# gige_phy.net
KiCad netlist of a schematic drawn in Altium Designer
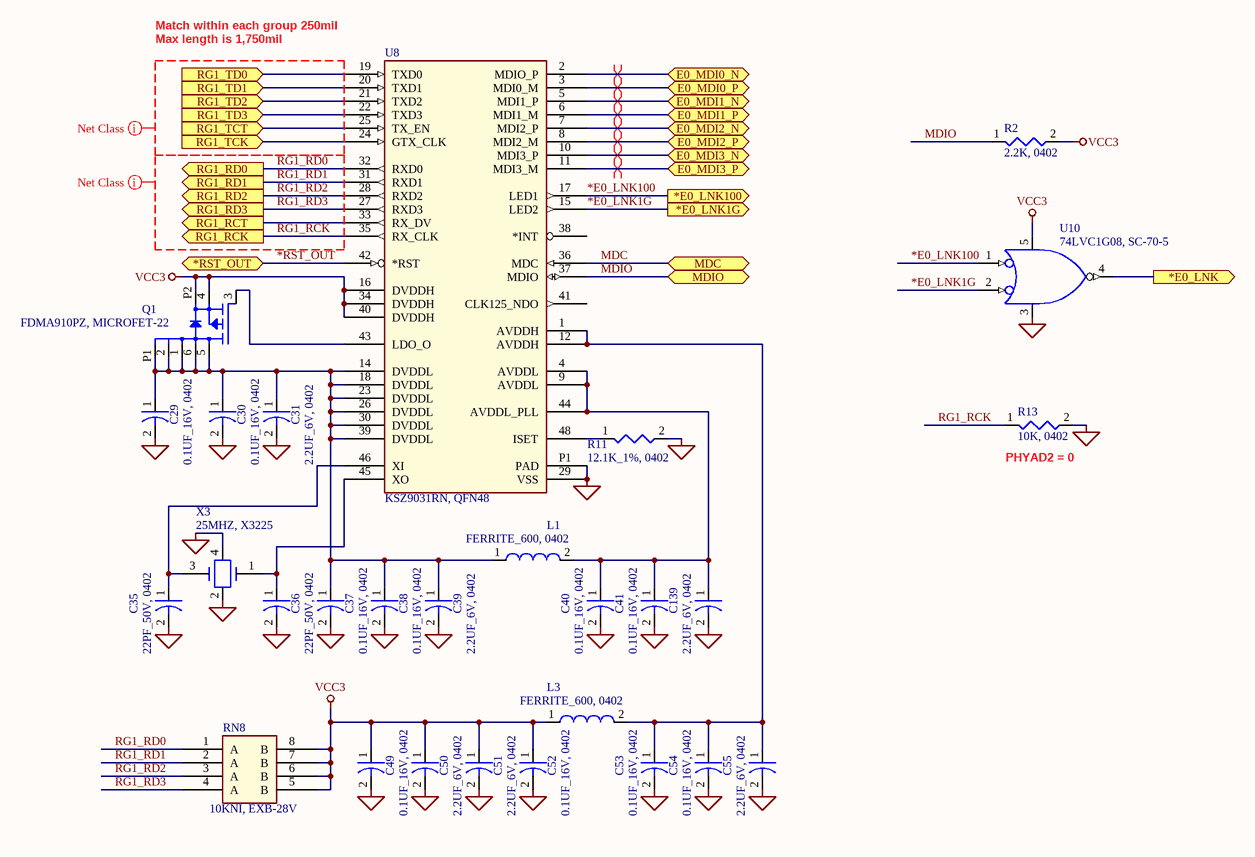
[diagram p0: gige_phy.SchDoc]

(export (version "E")
  (design (tool "Eeschema 10.0.6"))
  (components
    (comp (ref "C29")
      (value "0.1UF_16V, 0402")
      (footprint "0402C")
      (description "CAP - 0402 PKG")
      (libsource (lib "COGENT_Library") (part "0.1UF_16V, 0402"))
    )
    (comp (ref "C30")
      (value "0.1UF_16V, 0402")
      (footprint "0402C")
      (description "CAP - 0402 PKG")
      (libsource (lib "COGENT_Library") (part "0.1UF_16V, 0402"))
    )
    (comp (ref "C31")
      (value "2.2UF_6V, 0402")
      (footprint "0402C")
      (description "CAP - 0402 PKG")
      (libsource (lib "COGENT_Library") (part "2.2UF_6V, 0402"))
    )
    (comp (ref "C35")
      (value "22PF_50V, 0402")
      (footprint "0402C")
      (description "CAP - 0402 PKG")
      (libsource (lib "COGENT_Library") (part "22PF_50V, 0402"))
    )
    (comp (ref "C36")
      (value "22PF_50V, 0402")
      (footprint "0402C")
      (description "CAP - 0402 PKG")
      (libsource (lib "COGENT_Library") (part "22PF_50V, 0402"))
    )
    (comp (ref "C37")
      (value "0.1UF_16V, 0402")
      (footprint "0402C")
      (description "CAP - 0402 PKG")
      (libsource (lib "COGENT_Library") (part "0.1UF_16V, 0402"))
    )
    (comp (ref "C38")
      (value "0.1UF_16V, 0402")
      (footprint "0402C")
      (description "CAP - 0402 PKG")
      (libsource (lib "COGENT_Library") (part "0.1UF_16V, 0402"))
    )
    (comp (ref "C39")
      (value "2.2UF_6V, 0402")
      (footprint "0402C")
      (description "CAP - 0402 PKG")
      (libsource (lib "COGENT_Library") (part "2.2UF_6V, 0402"))
    )
    (comp (ref "C40")
      (value "0.1UF_16V, 0402")
      (footprint "0402C")
      (description "CAP - 0402 PKG")
      (libsource (lib "COGENT_Library") (part "0.1UF_16V, 0402"))
    )
    (comp (ref "C41")
      (value "0.1UF_16V, 0402")
      (footprint "0402C")
      (description "CAP - 0402 PKG")
      (libsource (lib "COGENT_Library") (part "0.1UF_16V, 0402"))
    )
    (comp (ref "C49")
      (value "0.1UF_16V, 0402")
      (footprint "0402C")
      (description "CAP - 0402 PKG")
      (libsource (lib "COGENT_Library") (part "0.1UF_16V, 0402"))
    )
    (comp (ref "C50")
      (value "2.2UF_6V, 0402")
      (footprint "0402C")
      (description "CAP - 0402 PKG")
      (libsource (lib "COGENT_Library") (part "2.2UF_6V, 0402"))
    )
    (comp (ref "C51")
      (value "2.2UF_6V, 0402")
      (footprint "0402C")
      (description "CAP - 0402 PKG")
      (libsource (lib "COGENT_Library") (part "2.2UF_6V, 0402"))
    )
    (comp (ref "C52")
      (value "0.1UF_16V, 0402")
      (footprint "0402C")
      (description "CAP - 0402 PKG")
      (libsource (lib "COGENT_Library") (part "0.1UF_16V, 0402"))
    )
    (comp (ref "C53")
      (value "0.1UF_16V, 0402")
      (footprint "0402C")
      (description "CAP - 0402 PKG")
      (libsource (lib "COGENT_Library") (part "0.1UF_16V, 0402"))
    )
    (comp (ref "C54")
      (value "0.1UF_16V, 0402")
      (footprint "0402C")
      (description "CAP - 0402 PKG")
      (libsource (lib "COGENT_Library") (part "0.1UF_16V, 0402"))
    )
    (comp (ref "C55")
      (value "2.2UF_6V, 0402")
      (footprint "0402C")
      (description "CAP - 0402 PKG")
      (libsource (lib "COGENT_Library") (part "2.2UF_6V, 0402"))
    )
    (comp (ref "C139")
      (value "2.2UF_6V, 0402")
      (footprint "0402C")
      (description "CAP - 0402 PKG")
      (libsource (lib "COGENT_Library") (part "2.2UF_6V, 0402"))
    )
    (comp (ref "L1")
      (value "FERRITE_600, 0402")
      (footprint "0402L")
      (description "FERRITE BEAD - 600 OHM, 300MA, 0402 PKG")
      (libsource (lib "COGENT_Library") (part "FERRITE_600, 0402"))
    )
    (comp (ref "L3")
      (value "FERRITE_600, 0402")
      (footprint "0402L")
      (description "FERRITE BEAD - 600 OHM, 300MA, 0402 PKG")
      (libsource (lib "COGENT_Library") (part "FERRITE_600, 0402"))
    )
    (comp (ref "Q1")
      (value "FDMA910PZ, MICROFET-22")
      (footprint "MICROFET-22")
      (description "P-FET - 20V, 7.2A @ 1.8Vgs, 34mohm")
      (libsource (lib "COGENT_Library") (part "FDMA910PZ, MICROFET-22"))
    )
    (comp (ref "R2")
      (value "2.2K, 0402")
      (footprint "0402R")
      (description "RES - 0402 PKG")
      (libsource (lib "COGENT_Library") (part "2.2K, 0402"))
    )
    (comp (ref "R11")
      (value "12.1K_1%, 0402")
      (footprint "0402R")
      (description "RES - 0402 PKG")
      (libsource (lib "COGENT_Library") (part "12.1K_1%, 0402"))
    )
    (comp (ref "R13")
      (value "10K, 0402")
      (footprint "0402R")
      (description "RES - 0402 PKG")
      (libsource (lib "COGENT_Library") (part "10K, 0402"))
    )
    (comp (ref "RN8")
      (value "10KNI, EXB-28V")
      (footprint "EXB-28V")
      (description "RES NET, 4 INDIVIDUAL, EXB-28V")
      (libsource (lib "COGENT_Library") (part "10KNI, EXB-28V"))
    )
    (comp (ref "U8")
      (value "KSZ9031RN, QFN48")
      (footprint "QFN48")
      (description "PHY - RGMII TO COPPER, 1.8V/3.3V I/O")
      (libsource (lib "COGENT_Library") (part "KSZ9031RN, QFN48"))
    )
    (comp (ref "U10")
      (value "74LVC1G08, SC-70-5")
      (footprint "SOT-353/SC-70-5")
      (description "GATE - 2-INPUT AND")
      (libsource (lib "COGENT_Library") (part "74LVC1G08, SC-70-5"))
    )
    (comp (ref "X3")
      (value "25MHZ, X3225")
      (footprint "X3225")
      (description "CRYSTAL - SMT, 3.2MM x 2.5MM, ABM8 PKG")
      (libsource (lib "COGENT_Library") (part "25MHZ, X3225"))
    )
  )
  (nets
    (net (code "1") (name "/*E0_LNK") (class "Default")
      (node (ref "U10") (pin "4") (pinfunction "Y_4") (pintype "output"))
    )
    (net (code "2") (name "/*E0_LNK1G") (class "Default")
      (node (ref "U10") (pin "2") (pinfunction "B_2") (pintype "input"))
      (node (ref "U8") (pin "15") (pinfunction "LED2_15") (pintype "output"))
    )
    (net (code "3") (name "/*E0_LNK100") (class "Default")
      (node (ref "U10") (pin "1") (pinfunction "A_1") (pintype "input"))
      (node (ref "U8") (pin "17") (pinfunction "LED1_17") (pintype "output"))
    )
    (net (code "4") (name "/*RST_OUT") (class "Default")
      (node (ref "U8") (pin "42") (pinfunction "*RST_42") (pintype "input"))
    )
    (net (code "5") (name "/E0_MDI0_N") (class "Default")
      (node (ref "U8") (pin "2") (pinfunction "MDIO_P_2") (pintype "passive"))
    )
    (net (code "6") (name "/E0_MDI0_P") (class "Default")
      (node (ref "U8") (pin "3") (pinfunction "MDI0_M_3") (pintype "passive"))
    )
    (net (code "7") (name "/E0_MDI1_N") (class "Default")
      (node (ref "U8") (pin "5") (pinfunction "MDI1_P_5") (pintype "passive"))
    )
    (net (code "8") (name "/E0_MDI1_P") (class "Default")
      (node (ref "U8") (pin "6") (pinfunction "MDI1_M_6") (pintype "passive"))
    )
    (net (code "9") (name "/E0_MDI2_N") (class "Default")
      (node (ref "U8") (pin "7") (pinfunction "MDI2_P_7") (pintype "passive"))
    )
    (net (code "10") (name "/E0_MDI2_P") (class "Default")
      (node (ref "U8") (pin "8") (pinfunction "MDI2_M_8") (pintype "passive"))
    )
    (net (code "11") (name "/E0_MDI3_N") (class "Default")
      (node (ref "U8") (pin "10") (pinfunction "MDI3_P_10") (pintype "passive"))
    )
    (net (code "12") (name "/E0_MDI3_P") (class "Default")
      (node (ref "U8") (pin "11") (pinfunction "MDI3_M_11") (pintype "passive"))
    )
    (net (code "13") (name "/MDC") (class "Default")
      (node (ref "U8") (pin "36") (pinfunction "MDC_36") (pintype "input"))
    )
    (net (code "14") (name "/MDIO") (class "Default")
      (node (ref "R2") (pin "1") (pinfunction "1_1") (pintype "passive"))
      (node (ref "U8") (pin "37") (pinfunction "MDIO_37") (pintype "bidirectional"))
    )
    (net (code "15") (name "/RG1_RCK") (class "Default")
      (node (ref "R13") (pin "1") (pinfunction "1_1") (pintype "passive"))
      (node (ref "U8") (pin "35") (pinfunction "RX_CLK_35") (pintype "output"))
    )
    (net (code "16") (name "/RG1_RCT") (class "Default")
      (node (ref "U8") (pin "33") (pinfunction "RX_DV_33") (pintype "output"))
    )
    (net (code "17") (name "/RG1_RD0") (class "Default")
      (node (ref "RN8") (pin "1") (pinfunction "A_1") (pintype "passive"))
      (node (ref "U8") (pin "32") (pinfunction "RXD0_32") (pintype "output"))
    )
    (net (code "18") (name "/RG1_RD1") (class "Default")
      (node (ref "RN8") (pin "2") (pinfunction "A_2") (pintype "passive"))
      (node (ref "U8") (pin "31") (pinfunction "RXD1_31") (pintype "output"))
    )
    (net (code "19") (name "/RG1_RD2") (class "Default")
      (node (ref "RN8") (pin "3") (pinfunction "A_3") (pintype "passive"))
      (node (ref "U8") (pin "28") (pinfunction "RXD2_28") (pintype "output"))
    )
    (net (code "20") (name "/RG1_RD3") (class "Default")
      (node (ref "RN8") (pin "4") (pinfunction "A_4") (pintype "passive"))
      (node (ref "U8") (pin "27") (pinfunction "RXD3_27") (pintype "output"))
    )
    (net (code "21") (name "/RG1_TCK") (class "Default")
      (node (ref "U8") (pin "24") (pinfunction "GTX_CLK_24") (pintype "input"))
    )
    (net (code "22") (name "/RG1_TCT") (class "Default")
      (node (ref "U8") (pin "25") (pinfunction "TX_EN_25") (pintype "input"))
    )
    (net (code "23") (name "/RG1_TD0") (class "Default")
      (node (ref "U8") (pin "19") (pinfunction "TXD0_19") (pintype "input"))
    )
    (net (code "24") (name "/RG1_TD1") (class "Default")
      (node (ref "U8") (pin "20") (pinfunction "TXD1_20") (pintype "input"))
    )
    (net (code "25") (name "/RG1_TD2") (class "Default")
      (node (ref "U8") (pin "21") (pinfunction "TXD2_21") (pintype "input"))
    )
    (net (code "26") (name "/RG1_TD3") (class "Default")
      (node (ref "U8") (pin "22") (pinfunction "TXD3_22") (pintype "input"))
    )
    (net (code "27") (name "GND") (class "Default")
      (node (ref "C139") (pin "2") (pinfunction "2_2") (pintype "passive"))
      (node (ref "C29") (pin "2") (pinfunction "2_2") (pintype "passive"))
      (node (ref "C30") (pin "2") (pinfunction "2_2") (pintype "passive"))
      (node (ref "C31") (pin "2") (pinfunction "2_2") (pintype "passive"))
      (node (ref "C35") (pin "2") (pinfunction "2_2") (pintype "passive"))
      (node (ref "C36") (pin "2") (pinfunction "2_2") (pintype "passive"))
      (node (ref "C37") (pin "2") (pinfunction "2_2") (pintype "passive"))
      (node (ref "C38") (pin "2") (pinfunction "2_2") (pintype "passive"))
      (node (ref "C39") (pin "2") (pinfunction "2_2") (pintype "passive"))
      (node (ref "C40") (pin "2") (pinfunction "2_2") (pintype "passive"))
      (node (ref "C41") (pin "2") (pinfunction "2_2") (pintype "passive"))
      (node (ref "C49") (pin "2") (pinfunction "2_2") (pintype "passive"))
      (node (ref "C50") (pin "2") (pinfunction "2_2") (pintype "passive"))
      (node (ref "C51") (pin "2") (pinfunction "2_2") (pintype "passive"))
      (node (ref "C52") (pin "2") (pinfunction "2_2") (pintype "passive"))
      (node (ref "C53") (pin "2") (pinfunction "2_2") (pintype "passive"))
      (node (ref "C54") (pin "2") (pinfunction "2_2") (pintype "passive"))
      (node (ref "C55") (pin "2") (pinfunction "2_2") (pintype "passive"))
      (node (ref "R11") (pin "2") (pinfunction "2_2") (pintype "passive"))
      (node (ref "R13") (pin "2") (pinfunction "2_2") (pintype "passive"))
      (node (ref "U10") (pin "3") (pinfunction "GND_3") (pintype "power_in"))
      (node (ref "U8") (pin "29") (pinfunction "VSS_29") (pintype "power_in"))
      (node (ref "U8") (pin "P1") (pinfunction "PAD_P1") (pintype "power_in"))
      (node (ref "X3") (pin "2") (pinfunction "2_2") (pintype "passive"))
      (node (ref "X3") (pin "4") (pinfunction "4_4") (pintype "passive"))
    )
    (net (code "28") (name "Net-(C53-Pad1)") (class "Default")
      (node (ref "C53") (pin "1") (pinfunction "1_1") (pintype "passive"))
      (node (ref "C54") (pin "1") (pinfunction "1_1") (pintype "passive"))
      (node (ref "C55") (pin "1") (pinfunction "1_1") (pintype "passive"))
      (node (ref "L3") (pin "2") (pinfunction "2_2") (pintype "passive"))
      (node (ref "U8") (pin "1") (pinfunction "AVDDH_1") (pintype "power_in"))
      (node (ref "U8") (pin "12") (pinfunction "AVDDH_12") (pintype "power_in"))
    )
    (net (code "29") (name "Net-(Q1-D1)") (class "Default")
      (node (ref "C29") (pin "1") (pinfunction "1_1") (pintype "passive"))
      (node (ref "C30") (pin "1") (pinfunction "1_1") (pintype "passive"))
      (node (ref "C31") (pin "1") (pinfunction "1_1") (pintype "passive"))
      (node (ref "C37") (pin "1") (pinfunction "1_1") (pintype "passive"))
      (node (ref "C38") (pin "1") (pinfunction "1_1") (pintype "passive"))
      (node (ref "C39") (pin "1") (pinfunction "1_1") (pintype "passive"))
      (node (ref "L1") (pin "1") (pinfunction "1_1") (pintype "passive"))
      (node (ref "Q1") (pin "1") (pinfunction "1_1") (pintype "passive"))
      (node (ref "Q1") (pin "2") (pinfunction "2_2") (pintype "passive"))
      (node (ref "Q1") (pin "5") (pinfunction "D1_5") (pintype "passive"))
      (node (ref "Q1") (pin "6") (pinfunction "D2_6") (pintype "passive"))
      (node (ref "Q1") (pin "P1") (pinfunction "D5_P1") (pintype "passive"))
      (node (ref "U8") (pin "14") (pinfunction "DVDDL_14") (pintype "power_in"))
      (node (ref "U8") (pin "18") (pinfunction "DVDDL_18") (pintype "power_in"))
      (node (ref "U8") (pin "23") (pinfunction "DVDDL_23") (pintype "power_in"))
      (node (ref "U8") (pin "26") (pinfunction "DVDDL_26") (pintype "power_in"))
      (node (ref "U8") (pin "30") (pinfunction "DVDDL_30") (pintype "power_in"))
      (node (ref "U8") (pin "39") (pinfunction "DVDDL_39") (pintype "power_in"))
    )
    (net (code "30") (name "Net-(U8-AVDDL_PLL)") (class "Default")
      (node (ref "C139") (pin "1") (pinfunction "1_1") (pintype "passive"))
      (node (ref "C40") (pin "1") (pinfunction "1_1") (pintype "passive"))
      (node (ref "C41") (pin "1") (pinfunction "1_1") (pintype "passive"))
      (node (ref "L1") (pin "2") (pinfunction "2_2") (pintype "passive"))
      (node (ref "U8") (pin "4") (pinfunction "AVDDL_4") (pintype "power_in"))
      (node (ref "U8") (pin "44") (pinfunction "AVDDL_PLL_44") (pintype "power_in"))
      (node (ref "U8") (pin "9") (pinfunction "AVDDL_9") (pintype "power_in"))
    )
    (net (code "31") (name "Net-(U8-ISET)") (class "Default")
      (node (ref "R11") (pin "1") (pinfunction "1_1") (pintype "passive"))
      (node (ref "U8") (pin "48") (pinfunction "ISET_48") (pintype "passive"))
    )
    (net (code "32") (name "Net-(U8-LDO_O)") (class "Default")
      (node (ref "Q1") (pin "3") (pinfunction "3_3") (pintype "passive"))
      (node (ref "U8") (pin "43") (pinfunction "LDO_O_43") (pintype "power_in"))
    )
    (net (code "33") (name "Net-(U8-XI)") (class "Default")
      (node (ref "C35") (pin "1") (pinfunction "1_1") (pintype "passive"))
      (node (ref "U8") (pin "46") (pinfunction "XI_46") (pintype "passive"))
      (node (ref "X3") (pin "3") (pinfunction "3_3") (pintype "passive"))
    )
    (net (code "34") (name "Net-(U8-XO)") (class "Default")
      (node (ref "C36") (pin "1") (pinfunction "1_1") (pintype "passive"))
      (node (ref "U8") (pin "45") (pinfunction "XO_45") (pintype "passive"))
      (node (ref "X3") (pin "1") (pinfunction "1_1") (pintype "passive"))
    )
    (net (code "35") (name "VCC3") (class "Default")
      (node (ref "C49") (pin "1") (pinfunction "1_1") (pintype "passive"))
      (node (ref "C50") (pin "1") (pinfunction "1_1") (pintype "passive"))
      (node (ref "C51") (pin "1") (pinfunction "1_1") (pintype "passive"))
      (node (ref "C52") (pin "1") (pinfunction "1_1") (pintype "passive"))
      (node (ref "L3") (pin "1") (pinfunction "1_1") (pintype "passive"))
      (node (ref "Q1") (pin "4") (pinfunction "4_4") (pintype "passive"))
      (node (ref "Q1") (pin "P2") (pinfunction "P2_P2") (pintype "passive"))
      (node (ref "R2") (pin "2") (pinfunction "2_2") (pintype "passive"))
      (node (ref "RN8") (pin "5") (pinfunction "B_5") (pintype "passive"))
      (node (ref "RN8") (pin "6") (pinfunction "B_6") (pintype "passive"))
      (node (ref "RN8") (pin "7") (pinfunction "B_7") (pintype "passive"))
      (node (ref "RN8") (pin "8") (pinfunction "B_8") (pintype "passive"))
      (node (ref "U10") (pin "5") (pinfunction "VCC3_5") (pintype "power_in"))
      (node (ref "U8") (pin "16") (pinfunction "DVDDH_16") (pintype "power_in"))
      (node (ref "U8") (pin "34") (pinfunction "DVDDH_34") (pintype "power_in"))
      (node (ref "U8") (pin "40") (pinfunction "DVDDH_40") (pintype "power_in"))
    )
    (net (code "36") (name "unconnected-(U8-*INT-Pad38)") (class "Default")
      (node (ref "U8") (pin "38") (pinfunction "*INT_38") (pintype "passive"))
    )
    (net (code "37") (name "unconnected-(U8-CLK125_NDO-Pad41)") (class "Default")
      (node (ref "U8") (pin "41") (pinfunction "CLK125_NDO_41") (pintype "output"))
    )
  )
)
